# ORD_CONNECTORS.net
KiCad netlist of a schematic drawn in Altium Designer
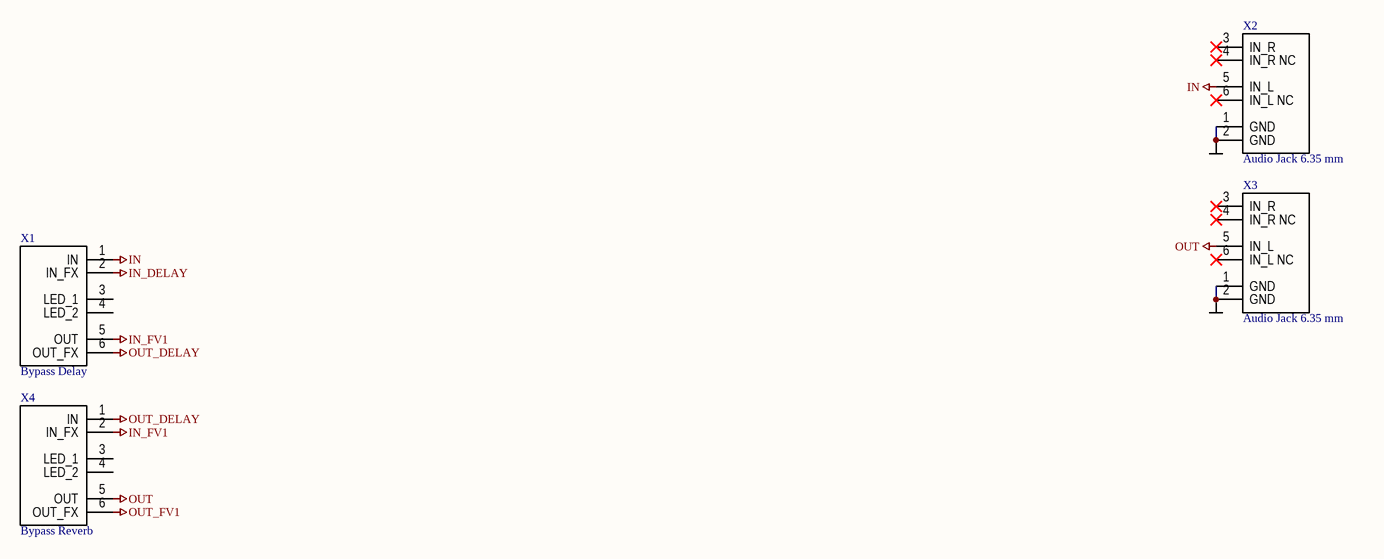
[diagram p0: ORD_CONNECTORS.SchDoc]

(export (version "E")
  (design (tool "Eeschema 10.0.6"))
  (components
    (comp (ref "X1")
      (value "Bypass Delay")
      (footprint "BYPASS PANEL")
      (description "Rele or 3PDT")
      (libsource (lib "Gost_connectors_lib") (part "Bypass"))
    )
    (comp (ref "X2")
      (value "Audio Jack 6.35 mm")
      (footprint "audio jack")
      (libsource (lib "Gost_connectors_lib") (part "Audio Jack"))
    )
    (comp (ref "X3")
      (value "Audio Jack 6.35 mm")
      (footprint "audio jack")
      (libsource (lib "Gost_connectors_lib") (part "Audio Jack"))
    )
    (comp (ref "X4")
      (value "Bypass Reverb")
      (footprint "BYPASS PANEL")
      (description "Rele or 3PDT")
      (libsource (lib "Gost_connectors_lib") (part "Bypass"))
    )
  )
  (nets
    (net (code "1") (name "GND") (class "Default")
      (node (ref "X2") (pin "1") (pinfunction "GND_1") (pintype "power_in"))
      (node (ref "X2") (pin "2") (pinfunction "GND_2") (pintype "power_in"))
      (node (ref "X3") (pin "1") (pinfunction "GND_1") (pintype "power_in"))
      (node (ref "X3") (pin "2") (pinfunction "GND_2") (pintype "power_in"))
    )
    (net (code "2") (name "IN") (class "Default")
      (node (ref "X1") (pin "1") (pinfunction "IN_1") (pintype "power_in"))
      (node (ref "X2") (pin "5") (pinfunction "IN_L_5") (pintype "power_in"))
    )
    (net (code "3") (name "IN_DELAY") (class "Default")
      (node (ref "X1") (pin "2") (pinfunction "IN_FX_2") (pintype "power_in"))
    )
    (net (code "4") (name "IN_FV1") (class "Default")
      (node (ref "X1") (pin "5") (pinfunction "OUT_5") (pintype "power_in"))
      (node (ref "X4") (pin "2") (pinfunction "IN_FX_2") (pintype "power_in"))
    )
    (net (code "5") (name "OUT") (class "Default")
      (node (ref "X3") (pin "5") (pinfunction "IN_L_5") (pintype "power_in"))
      (node (ref "X4") (pin "5") (pinfunction "OUT_5") (pintype "power_in"))
    )
    (net (code "6") (name "OUT_DELAY") (class "Default")
      (node (ref "X1") (pin "6") (pinfunction "OUT_FX_6") (pintype "power_in"))
      (node (ref "X4") (pin "1") (pinfunction "IN_1") (pintype "power_in"))
    )
    (net (code "7") (name "OUT_FV1") (class "Default")
      (node (ref "X4") (pin "6") (pinfunction "OUT_FX_6") (pintype "power_in"))
    )
    (net (code "8") (name "unconnected-(X1-LED_1-Pad3)") (class "Default")
      (node (ref "X1") (pin "3") (pinfunction "LED_1_3") (pintype "power_in"))
    )
    (net (code "9") (name "unconnected-(X1-LED_2-Pad4)") (class "Default")
      (node (ref "X1") (pin "4") (pinfunction "LED_2_4") (pintype "power_in"))
    )
    (net (code "10") (name "unconnected-(X2-IN_L_NC-Pad6)") (class "Default")
      (node (ref "X2") (pin "6") (pinfunction "IN_L_NC_6") (pintype "power_in+no_connect"))
    )
    (net (code "11") (name "unconnected-(X2-IN_R-Pad3)") (class "Default")
      (node (ref "X2") (pin "3") (pinfunction "IN_R_3") (pintype "power_in+no_connect"))
    )
    (net (code "12") (name "unconnected-(X2-IN_R_NC-Pad4)") (class "Default")
      (node (ref "X2") (pin "4") (pinfunction "IN_R_NC_4") (pintype "power_in+no_connect"))
    )
    (net (code "13") (name "unconnected-(X3-IN_L_NC-Pad6)") (class "Default")
      (node (ref "X3") (pin "6") (pinfunction "IN_L_NC_6") (pintype "power_in+no_connect"))
    )
    (net (code "14") (name "unconnected-(X3-IN_R-Pad3)") (class "Default")
      (node (ref "X3") (pin "3") (pinfunction "IN_R_3") (pintype "power_in+no_connect"))
    )
    (net (code "15") (name "unconnected-(X3-IN_R_NC-Pad4)") (class "Default")
      (node (ref "X3") (pin "4") (pinfunction "IN_R_NC_4") (pintype "power_in+no_connect"))
    )
    (net (code "16") (name "unconnected-(X4-LED_1-Pad3)") (class "Default")
      (node (ref "X4") (pin "3") (pinfunction "LED_1_3") (pintype "power_in"))
    )
    (net (code "17") (name "unconnected-(X4-LED_2-Pad4)") (class "Default")
      (node (ref "X4") (pin "4") (pinfunction "LED_2_4") (pintype "power_in"))
    )
  )
)
